# MicroSpecSensorBoard_switch_V2_1.net
KiCad netlist of a schematic drawn in Altium Designer
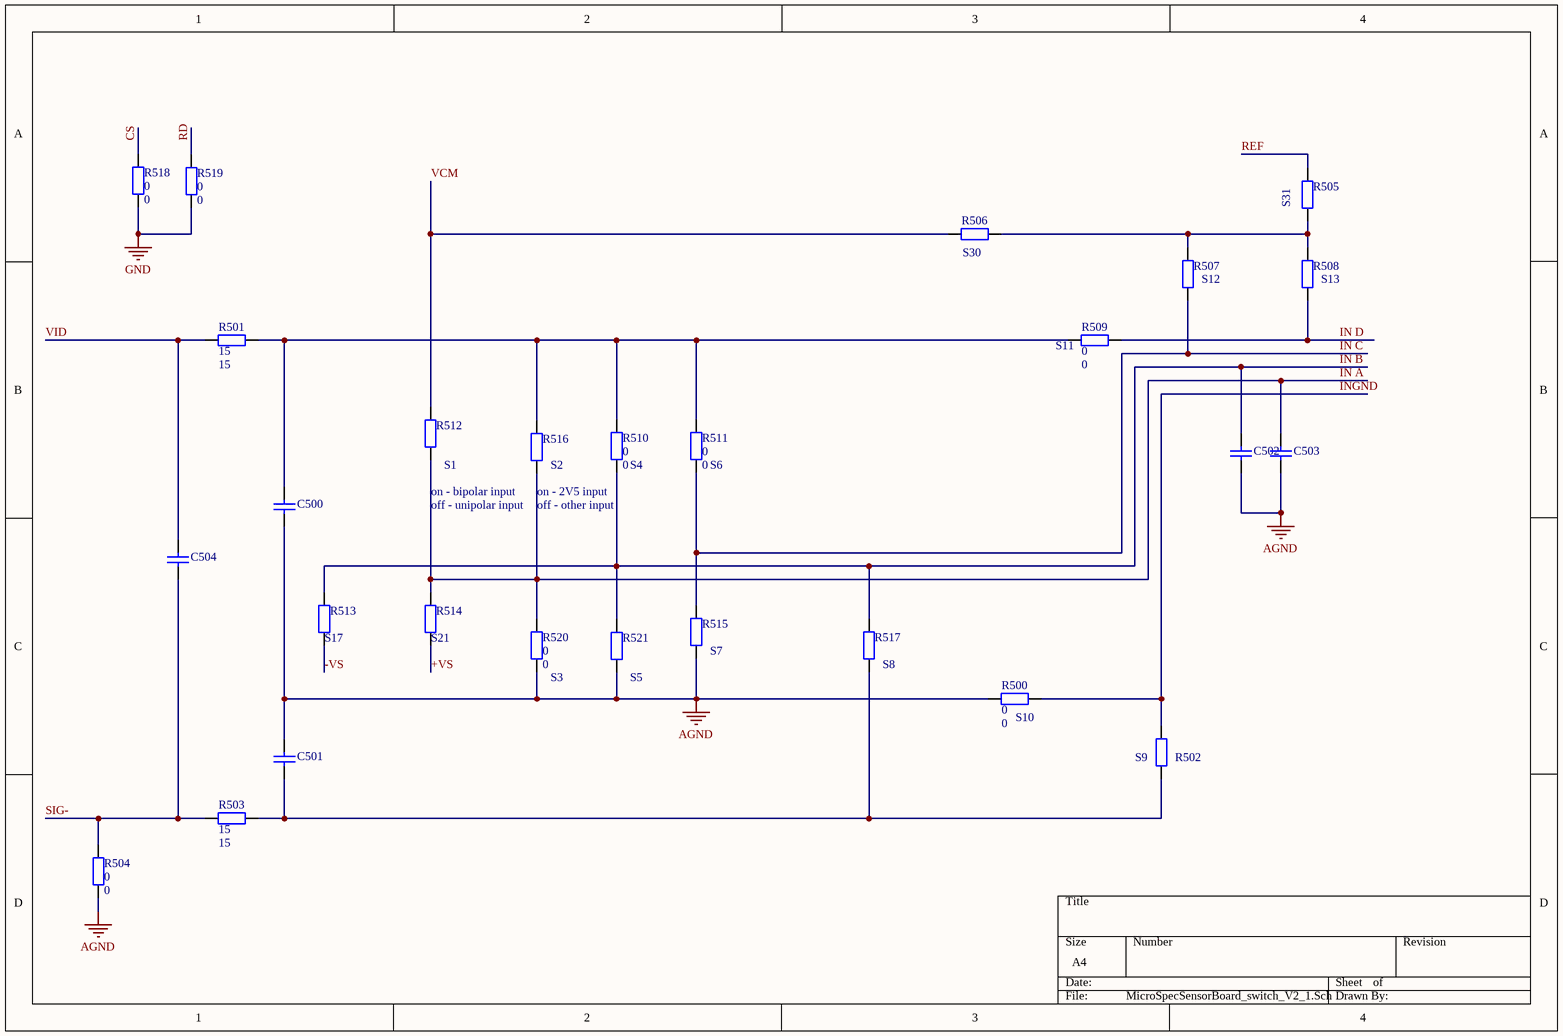
[diagram p0: MicroSpecSensorBoard_switch_V2_1.SchDoc]

(export (version "E")
  (design (tool "Eeschema 10.0.6"))
  (components
    (comp (ref "C500")
      (value "~")
      (footprint "6-0805_N")
      (description "Capacitor not populated")
      (fields (field (name "PUBLISHER") "Altium Limited"))
      (libsource (lib "USER_Library") (part "Cap_1"))
    )
    (comp (ref "C501")
      (value "~")
      (footprint "6-0805_N")
      (description "Capacitor not populated")
      (fields (field (name "PUBLISHER") "Altium Limited"))
      (libsource (lib "USER_Library") (part "Cap_1"))
    )
    (comp (ref "C502")
      (value "~")
      (footprint "6-0805_N")
      (description "Capacitor not populated")
      (fields (field (name "PUBLISHER") "Altium Limited"))
      (libsource (lib "USER_Library") (part "Cap_1"))
    )
    (comp (ref "C503")
      (value "~")
      (footprint "6-0805_N")
      (description "Capacitor not populated")
      (fields (field (name "PUBLISHER") "Altium Limited"))
      (libsource (lib "USER_Library") (part "Cap_1"))
    )
    (comp (ref "C504")
      (value "~")
      (footprint "6-0805_N")
      (description "Capacitor not populated")
      (fields (field (name "PUBLISHER") "Altium Limited"))
      (libsource (lib "USER_Library") (part "Cap_1"))
    )
    (comp (ref "R500")
      (value "0")
      (footprint "6-0805_M")
      (description "Resistor_S10 -place")
      (fields (field (name "ALTIUM_VALUE") "0") (field (name "PUBLISHER") "Altium Limited"))
      (libsource (lib "") (part "Res2_2"))
    )
    (comp (ref "R501")
      (value "15")
      (footprint "6-0805_L")
      (description "Resistor")
      (fields (field (name "ALTIUM_VALUE") "15") (field (name "PUBLISHER") "Altium Limited"))
      (libsource (lib "") (part "Res2_2"))
    )
    (comp (ref "R502")
      (value "~")
      (footprint "6-0805_M")
      (description "Resistor_S9 - not place")
      (fields (field (name "PUBLISHER") "Altium Limited"))
      (libsource (lib "USER_Library") (part "Res2"))
    )
    (comp (ref "R503")
      (value "15")
      (footprint "6-0805_L")
      (description "Resistor")
      (fields (field (name "ALTIUM_VALUE") "15") (field (name "PUBLISHER") "Altium Limited"))
      (libsource (lib "") (part "Res2_2"))
    )
    (comp (ref "R504")
      (value "0")
      (footprint "6-0805_L")
      (description "Resistor")
      (fields (field (name "ALTIUM_VALUE") "0") (field (name "PUBLISHER") "Altium Limited"))
      (libsource (lib "USER_Library") (part "Res2"))
    )
    (comp (ref "R505")
      (value "~")
      (footprint "6-0805_M")
      (description "Resistor_S31 -not place")
      (fields (field (name "PUBLISHER") "Altium Limited"))
      (libsource (lib "USER_Library") (part "Res2"))
    )
    (comp (ref "R506")
      (value "~")
      (footprint "6-0805_M")
      (description "Resistor_S30 -not place")
      (fields (field (name "PUBLISHER") "Altium Limited"))
      (libsource (lib "") (part "Res2_2"))
    )
    (comp (ref "R507")
      (value "~")
      (footprint "6-0805_M")
      (description "Resistor_S12 -not place")
      (fields (field (name "PUBLISHER") "Altium Limited"))
      (libsource (lib "USER_Library") (part "Res2"))
    )
    (comp (ref "R508")
      (value "~")
      (footprint "6-0805_M")
      (description "Resistor_S13 -not place")
      (fields (field (name "PUBLISHER") "Altium Limited"))
      (libsource (lib "USER_Library") (part "Res2"))
    )
    (comp (ref "R509")
      (value "0")
      (footprint "6-0805_M")
      (description "Resistor_S11 -place")
      (fields (field (name "ALTIUM_VALUE") "0") (field (name "PUBLISHER") "Altium Limited"))
      (libsource (lib "") (part "Res2_2"))
    )
    (comp (ref "R510")
      (value "0")
      (footprint "6-0805_M")
      (description "Resistor_S4 -place")
      (fields (field (name "ALTIUM_VALUE") "0") (field (name "PUBLISHER") "Altium Limited"))
      (libsource (lib "") (part "Res2_1"))
    )
    (comp (ref "R511")
      (value "0")
      (footprint "6-0805_M")
      (description "Resistor_S6 -place")
      (fields (field (name "ALTIUM_VALUE") "0") (field (name "PUBLISHER") "Altium Limited"))
      (libsource (lib "") (part "Res2_1"))
    )
    (comp (ref "R512")
      (value "~")
      (footprint "6-0805_M")
      (description "Resistor_S1 -not place")
      (fields (field (name "PUBLISHER") "Altium Limited"))
      (libsource (lib "USER_Library") (part "Res2"))
    )
    (comp (ref "R513")
      (value "~")
      (footprint "6-0805_M")
      (description "Resistor_S17 -not place")
      (fields (field (name "PUBLISHER") "Altium Limited"))
      (libsource (lib "USER_Library") (part "Res2"))
    )
    (comp (ref "R514")
      (value "~")
      (footprint "6-0805_M")
      (description "Resistor_S21 -not place")
      (fields (field (name "PUBLISHER") "Altium Limited"))
      (libsource (lib "USER_Library") (part "Res2"))
    )
    (comp (ref "R515")
      (value "~")
      (footprint "6-0805_M")
      (description "Resistor_Spt7 -not place")
      (fields (field (name "PUBLISHER") "Altium Limited"))
      (libsource (lib "USER_Library") (part "Res2"))
    )
    (comp (ref "R516")
      (value "~")
      (footprint "6-0805_M")
      (description "Resistor_S2 -not place")
      (fields (field (name "PUBLISHER") "Altium Limited"))
      (libsource (lib "USER_Library") (part "Res2"))
    )
    (comp (ref "R517")
      (value "~")
      (footprint "6-0805_M")
      (description "Resistor_S8 -not place")
      (fields (field (name "PUBLISHER") "Altium Limited"))
      (libsource (lib "USER_Library") (part "Res2"))
    )
    (comp (ref "R518")
      (value "0")
      (footprint "6-0805_M")
      (description "Resistor_CS -place")
      (fields (field (name "ALTIUM_VALUE") "0") (field (name "PUBLISHER") "Altium Limited"))
      (libsource (lib "USER_Library") (part "Res2"))
    )
    (comp (ref "R519")
      (value "0")
      (footprint "6-0805_M")
      (description "Resistor_RD -place")
      (fields (field (name "ALTIUM_VALUE") "0") (field (name "PUBLISHER") "Altium Limited"))
      (libsource (lib "USER_Library") (part "Res2"))
    )
    (comp (ref "R520")
      (value "0")
      (footprint "6-0805_M")
      (description "Resistor_S3 -place")
      (fields (field (name "ALTIUM_VALUE") "0") (field (name "PUBLISHER") "Altium Limited"))
      (libsource (lib "") (part "Res2_1"))
    )
    (comp (ref "R521")
      (value "~")
      (footprint "6-0805_M")
      (description "Resistor_S5 -not place")
      (fields (field (name "PUBLISHER") "Altium Limited"))
      (libsource (lib "USER_Library") (part "Res2"))
    )
  )
  (nets
    (net (code "1") (name "/+VS") (class "Default")
      (node (ref "R514") (pin "1") (pinfunction "1_1") (pintype "passive"))
    )
    (net (code "2") (name "/-VS") (class "Default")
      (node (ref "R513") (pin "1") (pinfunction "1_1") (pintype "passive"))
    )
    (net (code "3") (name "/CS") (class "Default")
      (node (ref "R518") (pin "2") (pinfunction "2_2") (pintype "passive"))
    )
    (net (code "4") (name "/IN A") (class "Default")
      (node (ref "C503") (pin "1") (pinfunction "1_1") (pintype "passive"))
      (node (ref "R512") (pin "1") (pinfunction "1_1") (pintype "passive"))
      (node (ref "R514") (pin "2") (pinfunction "2_2") (pintype "passive"))
      (node (ref "R516") (pin "1") (pinfunction "1_1") (pintype "passive"))
      (node (ref "R520") (pin "1") (pinfunction "1_1") (pintype "passive"))
    )
    (net (code "5") (name "/IN B") (class "Default")
      (node (ref "C502") (pin "1") (pinfunction "1_1") (pintype "passive"))
      (node (ref "R510") (pin "2") (pinfunction "2_2") (pintype "passive"))
      (node (ref "R513") (pin "2") (pinfunction "2_2") (pintype "passive"))
      (node (ref "R517") (pin "2") (pinfunction "2_2") (pintype "passive"))
      (node (ref "R521") (pin "2") (pinfunction "2_2") (pintype "passive"))
    )
    (net (code "6") (name "/IN C") (class "Default")
      (node (ref "R507") (pin "1") (pinfunction "1_1") (pintype "passive"))
      (node (ref "R511") (pin "2") (pinfunction "2_2") (pintype "passive"))
      (node (ref "R515") (pin "2") (pinfunction "2_2") (pintype "passive"))
    )
    (net (code "7") (name "/IN D") (class "Default")
      (node (ref "R508") (pin "1") (pinfunction "1_1") (pintype "passive"))
      (node (ref "R509") (pin "2") (pinfunction "2_2") (pintype "passive"))
    )
    (net (code "8") (name "/INGND") (class "Default")
      (node (ref "R500") (pin "2") (pinfunction "2_2") (pintype "passive"))
      (node (ref "R502") (pin "2") (pinfunction "2_2") (pintype "passive"))
    )
    (net (code "9") (name "/RD") (class "Default")
      (node (ref "R519") (pin "2") (pinfunction "2_2") (pintype "passive"))
    )
    (net (code "10") (name "/REF") (class "Default")
      (node (ref "R505") (pin "2") (pinfunction "2_2") (pintype "passive"))
    )
    (net (code "11") (name "/SIG-") (class "Default")
      (node (ref "C504") (pin "2") (pinfunction "2_2") (pintype "passive"))
      (node (ref "R503") (pin "1") (pinfunction "1_1") (pintype "passive"))
      (node (ref "R504") (pin "2") (pinfunction "2_2") (pintype "passive"))
    )
    (net (code "12") (name "/VCM") (class "Default")
      (node (ref "R506") (pin "1") (pinfunction "1_1") (pintype "passive"))
      (node (ref "R512") (pin "2") (pinfunction "2_2") (pintype "passive"))
    )
    (net (code "13") (name "/VID") (class "Default")
      (node (ref "C504") (pin "1") (pinfunction "1_1") (pintype "passive"))
      (node (ref "R501") (pin "1") (pinfunction "1_1") (pintype "passive"))
    )
    (net (code "14") (name "AGND") (class "Default")
      (node (ref "C500") (pin "2") (pinfunction "2_2") (pintype "passive"))
      (node (ref "C501") (pin "1") (pinfunction "1_1") (pintype "passive"))
      (node (ref "C502") (pin "2") (pinfunction "2_2") (pintype "passive"))
      (node (ref "C503") (pin "2") (pinfunction "2_2") (pintype "passive"))
      (node (ref "R500") (pin "1") (pinfunction "1_1") (pintype "passive"))
      (node (ref "R504") (pin "1") (pinfunction "1_1") (pintype "passive"))
      (node (ref "R515") (pin "1") (pinfunction "1_1") (pintype "passive"))
      (node (ref "R520") (pin "2") (pinfunction "2_2") (pintype "passive"))
      (node (ref "R521") (pin "1") (pinfunction "1_1") (pintype "passive"))
    )
    (net (code "15") (name "GND") (class "Default")
      (node (ref "R518") (pin "1") (pinfunction "1_1") (pintype "passive"))
      (node (ref "R519") (pin "1") (pinfunction "1_1") (pintype "passive"))
    )
    (net (code "16") (name "Net-(C500-Pad1)") (class "Default")
      (node (ref "C500") (pin "1") (pinfunction "1_1") (pintype "passive"))
      (node (ref "R501") (pin "2") (pinfunction "2_2") (pintype "passive"))
      (node (ref "R509") (pin "1") (pinfunction "1_1") (pintype "passive"))
      (node (ref "R510") (pin "1") (pinfunction "1_1") (pintype "passive"))
      (node (ref "R511") (pin "1") (pinfunction "1_1") (pintype "passive"))
      (node (ref "R516") (pin "2") (pinfunction "2_2") (pintype "passive"))
    )
    (net (code "17") (name "Net-(C501-Pad2)") (class "Default")
      (node (ref "C501") (pin "2") (pinfunction "2_2") (pintype "passive"))
      (node (ref "R502") (pin "1") (pinfunction "1_1") (pintype "passive"))
      (node (ref "R503") (pin "2") (pinfunction "2_2") (pintype "passive"))
      (node (ref "R517") (pin "1") (pinfunction "1_1") (pintype "passive"))
    )
    (net (code "18") (name "Net-(R505-Pad1)") (class "Default")
      (node (ref "R505") (pin "1") (pinfunction "1_1") (pintype "passive"))
      (node (ref "R506") (pin "2") (pinfunction "2_2") (pintype "passive"))
      (node (ref "R507") (pin "2") (pinfunction "2_2") (pintype "passive"))
      (node (ref "R508") (pin "2") (pinfunction "2_2") (pintype "passive"))
    )
  )
)
